# Vref.net
KiCad netlist of a schematic drawn in Altium Designer
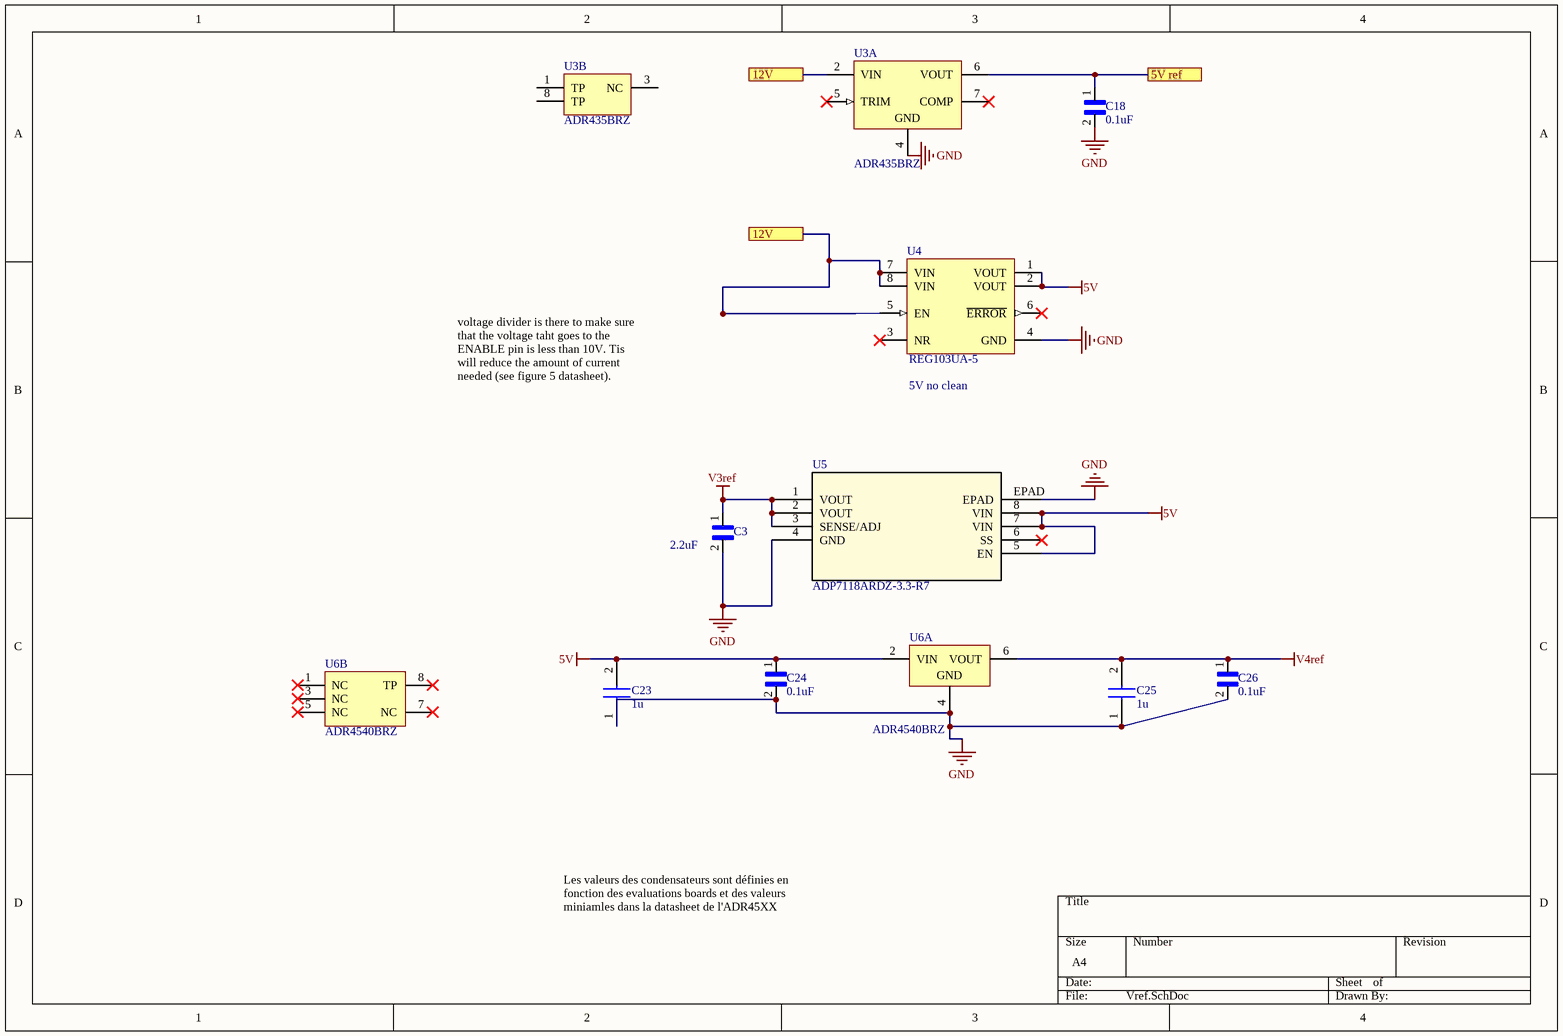
[diagram p0: Vref.SchDoc]

(export (version "E")
  (design (tool "Eeschema 10.0.6"))
  (components
    (comp (ref "C3")
      (value "2.2uF")
      (footprint "CAPC1608X90")
      (description "2.2UF 16V 20%")
      (fields
        (field (name "MP") "F981C225MMA")
        (field (name "MF") "{'manufacturer': u'AVX'}")
        (field (name "SOURCE") "workerBoard.SCHLIB")
      )
      (libsource (lib "GIGUL") (part "Symbol"))
    )
    (comp (ref "C18")
      (value "0.1uF")
      (footprint "CAPC1608X90N")
      (description "Cap Ceramic 0.1uF 25V X5R 10% SMD 0603 85ÂÂŽ T/R")
      (fields
        (field (name "MP") "06033D104KAT2A")
        (field (name "MF") "{'manufacturer': u'AVX'}")
        (field (name "SOURCE") "workerBoard.SCHLIB")
      )
      (libsource (lib "GIGUL") (part "06033D104KAT2A"))
    )
    (comp (ref "C23")
      (value "1u")
      (footprint "CAPC1608X90N")
      (description "Capacitor")
      (fields
        (field (name "MANUFACTURER_PART_NUMBER") "0603YC105MAT4A")
        (field (name "SOURCE") "workerBoard.SCHLIB")
      )
      (libsource (lib "GIGUL") (part "0603YC105MAT4A"))
    )
    (comp (ref "C24")
      (value "0.1uF")
      (footprint "CAPC1608X90N")
      (description "Cap Ceramic 0.1uF 25V X5R 10% SMD 0603 85ÂÂŽ T/R")
      (fields
        (field (name "MP") "06033D104KAT2A")
        (field (name "MF") "{'manufacturer': u'AVX'}")
        (field (name "SOURCE") "workerBoard.SCHLIB")
      )
      (libsource (lib "GIGUL") (part "06033D104KAT2A"))
    )
    (comp (ref "C25")
      (value "1u")
      (footprint "CAPC1608X90N")
      (description "Capacitor")
      (fields
        (field (name "MANUFACTURER_PART_NUMBER") "0603YC105MAT4A")
        (field (name "SOURCE") "workerBoard.SCHLIB")
      )
      (libsource (lib "GIGUL") (part "0603YC105MAT4A"))
    )
    (comp (ref "C26")
      (value "0.1uF")
      (footprint "CAPC1608X90N")
      (description "Cap Ceramic 0.1uF 25V X5R 10% SMD 0603 85ÂÂŽ T/R")
      (fields
        (field (name "MP") "06033D104KAT2A")
        (field (name "MF") "{'manufacturer': u'AVX'}")
        (field (name "SOURCE") "workerBoard.SCHLIB")
      )
      (libsource (lib "GIGUL") (part "06033D104KAT2A"))
    )
    (comp (ref "U3")
      (value "ADR435BRZ")
      (footprint "ADI-R-8_M")
      (fields (field (name "MANUFACTURER") "Analog Devices") (field (name "SOURCE") "workerBoard.SCHLIB"))
      (libsource (lib "GIGUL") (part "CMP-0784-00226-1"))
    )
    (comp (ref "U4")
      (value "REG103UA-5")
      (footprint "D0008A_M")
      (fields (field (name "MANUFACTURER") "Texas Instruments") (field (name "SOURCE") "workerBoard.SCHLIB"))
      (libsource (lib "GIGUL") (part "CMP-0395-00135-2"))
    )
    (comp (ref "U5")
      (value "ADP7118ARDZ-3.3-R7")
      (footprint "SOIC_08_EP_3P9X4P9_ADI")
      (description "No Description Available")
      (fields
        (field (name "COPYRIGHT") "Copyright (C) 2021 Ultra Librarian. All rights reserved.")
        (field (name "SOURCE") "workerBoard.SCHLIB")
      )
      (libsource (lib "GIGUL") (part "ADP7118ARDZ-3.3-R7"))
    )
    (comp (ref "U6")
      (value "ADR4540BRZ")
      (footprint "ADI-R-8_M")
      (fields (field (name "MANUFACTURER") "Analog Devices") (field (name "SOURCE") "workerBoard.SCHLIB"))
      (libsource (lib "GIGUL") (part "CMP-0784-00192-1"))
    )
  )
  (nets
    (net (code "1") (name "/5V ref") (class "Default")
      (node (ref "C18") (pin "1") (pinfunction "1_1") (pintype "passive"))
      (node (ref "U3") (pin "6") (pinfunction "VOUT_6") (pintype "power_in"))
    )
    (net (code "2") (name "/12V") (class "Default")
      (node (ref "U3") (pin "2") (pinfunction "VIN_2") (pintype "power_in"))
      (node (ref "U4") (pin "5") (pinfunction "EN_5") (pintype "input"))
      (node (ref "U4") (pin "7") (pinfunction "VIN_7") (pintype "power_in"))
      (node (ref "U4") (pin "8") (pinfunction "VIN_8") (pintype "power_in"))
    )
    (net (code "3") (name "5V") (class "Default")
      (node (ref "C23") (pin "2") (pinfunction "2_2") (pintype "passive"))
      (node (ref "C24") (pin "1") (pinfunction "1_1") (pintype "passive"))
      (node (ref "U4") (pin "1") (pinfunction "VOUT_1") (pintype "power_in"))
      (node (ref "U4") (pin "2") (pinfunction "VOUT_2") (pintype "power_in"))
      (node (ref "U5") (pin "5") (pinfunction "EN_5") (pintype "passive"))
      (node (ref "U5") (pin "7") (pinfunction "VIN_7") (pintype "passive"))
      (node (ref "U5") (pin "8") (pinfunction "VIN_8") (pintype "passive"))
      (node (ref "U6") (pin "2") (pinfunction "VIN_2") (pintype "power_in"))
    )
    (net (code "4") (name "GND") (class "Default")
      (node (ref "C18") (pin "2") (pinfunction "2_2") (pintype "passive"))
      (node (ref "C23") (pin "1") (pinfunction "1_1") (pintype "passive"))
      (node (ref "C24") (pin "2") (pinfunction "2_2") (pintype "passive"))
      (node (ref "C25") (pin "1") (pinfunction "1_1") (pintype "passive"))
      (node (ref "C26") (pin "2") (pinfunction "2_2") (pintype "passive"))
      (node (ref "C3") (pin "2") (pinfunction "2_2") (pintype "passive"))
      (node (ref "U3") (pin "4") (pinfunction "GND_4") (pintype "power_in"))
      (node (ref "U4") (pin "4") (pinfunction "GND_4") (pintype "power_in"))
      (node (ref "U5") (pin "4") (pinfunction "GND_4") (pintype "passive"))
      (node (ref "U5") (pin "EPAD") (pinfunction "EPAD_EPAD") (pintype "passive"))
      (node (ref "U6") (pin "4") (pinfunction "GND_4") (pintype "power_in"))
    )
    (net (code "5") (name "V3ref") (class "Default")
      (node (ref "C3") (pin "1") (pinfunction "1_1") (pintype "passive"))
      (node (ref "U5") (pin "1") (pinfunction "VOUT_1") (pintype "power_in"))
      (node (ref "U5") (pin "2") (pinfunction "VOUT_2") (pintype "power_in"))
      (node (ref "U5") (pin "3") (pinfunction "SENSE/ADJ_3") (pintype "passive"))
    )
    (net (code "6") (name "V4ref") (class "Default")
      (node (ref "C25") (pin "2") (pinfunction "2_2") (pintype "passive"))
      (node (ref "C26") (pin "1") (pinfunction "1_1") (pintype "passive"))
      (node (ref "U6") (pin "6") (pinfunction "VOUT_6") (pintype "power_in"))
    )
    (net (code "7") (name "unconnected-(U3A-COMP-Pad7)") (class "Default")
      (node (ref "U3") (pin "7") (pinfunction "COMP_7") (pintype "passive+no_connect"))
    )
    (net (code "8") (name "unconnected-(U3A-TRIM-Pad5)") (class "Default")
      (node (ref "U3") (pin "5") (pinfunction "TRIM_5") (pintype "input+no_connect"))
    )
    (net (code "9") (name "unconnected-(U3B-NC-Pad3)") (class "Default")
      (node (ref "U3") (pin "3") (pinfunction "NC_3") (pintype "passive"))
    )
    (net (code "10") (name "unconnected-(U3B-TP-Pad1)") (class "Default")
      (node (ref "U3") (pin "1") (pinfunction "TP_1") (pintype "passive"))
    )
    (net (code "11") (name "unconnected-(U3B-TP-Pad8)") (class "Default")
      (node (ref "U3") (pin "8") (pinfunction "TP_8") (pintype "passive"))
    )
    (net (code "12") (name "unconnected-(U4-NR-Pad3)") (class "Default")
      (node (ref "U4") (pin "3") (pinfunction "NR_3") (pintype "passive+no_connect"))
    )
    (net (code "13") (name "unconnected-(U4-~{ERROR}-Pad6)") (class "Default")
      (node (ref "U4") (pin "6") (pinfunction "~{ERROR}_6") (pintype "output+no_connect"))
    )
    (net (code "14") (name "unconnected-(U5-SS-Pad6)") (class "Default")
      (node (ref "U5") (pin "6") (pinfunction "SS_6") (pintype "passive+no_connect"))
    )
    (net (code "15") (name "unconnected-(U6B-NC-Pad1)") (class "Default")
      (node (ref "U6") (pin "1") (pinfunction "NC_1") (pintype "passive+no_connect"))
    )
    (net (code "16") (name "unconnected-(U6B-NC-Pad3)") (class "Default")
      (node (ref "U6") (pin "3") (pinfunction "NC_3") (pintype "passive+no_connect"))
    )
    (net (code "17") (name "unconnected-(U6B-NC-Pad5)") (class "Default")
      (node (ref "U6") (pin "5") (pinfunction "NC_5") (pintype "passive+no_connect"))
    )
    (net (code "18") (name "unconnected-(U6B-NC-Pad7)") (class "Default")
      (node (ref "U6") (pin "7") (pinfunction "NC_7") (pintype "passive+no_connect"))
    )
    (net (code "19") (name "unconnected-(U6B-TP-Pad8)") (class "Default")
      (node (ref "U6") (pin "8") (pinfunction "TP_8") (pintype "passive+no_connect"))
    )
  )
)
